# SwitchedATXBreakout.net
KiCad netlist of a schematic drawn in EAGLE
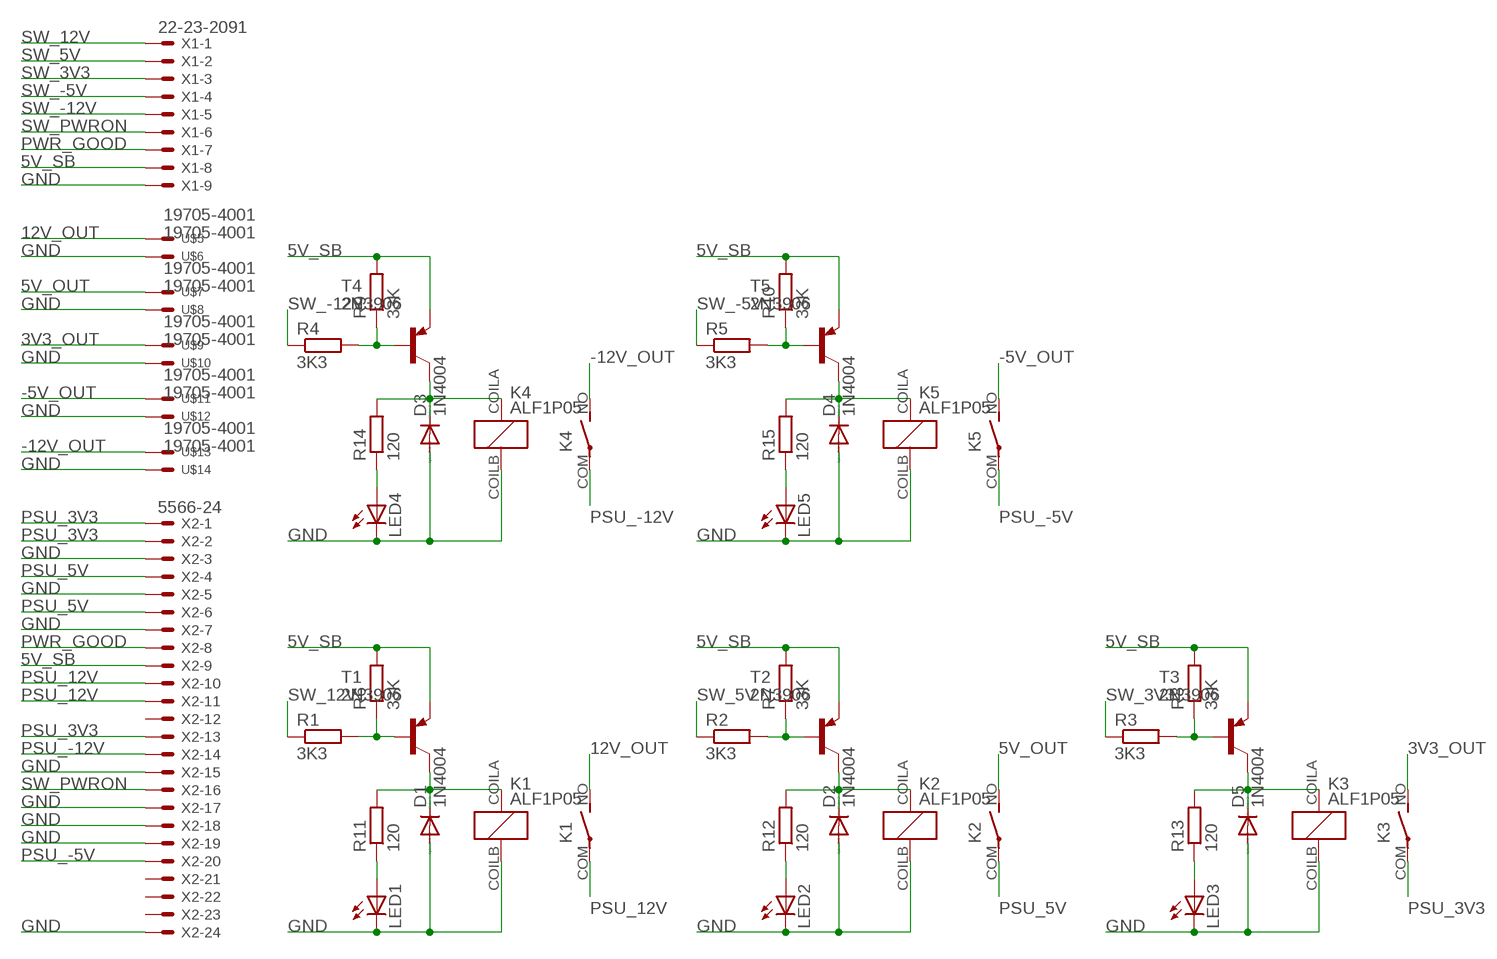
[diagram p0: schematic, sheet 1]

(export (version "E")
  (design (tool "Eeschema 10.0.6"))
  (components
    (comp (ref "D1")
      (value "1N4004")
      (footprint "eagle-import:DO41-10")
      (libsource (lib "eagle-import") (part "1N4004"))
    )
    (comp (ref "D2")
      (value "1N4004")
      (footprint "eagle-import:DO41-10")
      (libsource (lib "eagle-import") (part "1N4004"))
    )
    (comp (ref "D3")
      (value "1N4004")
      (footprint "eagle-import:DO41-10")
      (libsource (lib "eagle-import") (part "1N4004"))
    )
    (comp (ref "D4")
      (value "1N4004")
      (footprint "eagle-import:DO41-10")
      (libsource (lib "eagle-import") (part "1N4004"))
    )
    (comp (ref "D5")
      (value "1N4004")
      (footprint "eagle-import:DO41-10")
      (libsource (lib "eagle-import") (part "1N4004"))
    )
    (comp (ref "K1")
      (value "ALF1P05")
      (footprint "eagle-import:ALF")
      (libsource (lib "eagle-import") (part "ALF1P05"))
    )
    (comp (ref "K2")
      (value "ALF1P05")
      (footprint "eagle-import:ALF")
      (libsource (lib "eagle-import") (part "ALF1P05"))
    )
    (comp (ref "K3")
      (value "ALF1P05")
      (footprint "eagle-import:ALF")
      (libsource (lib "eagle-import") (part "ALF1P05"))
    )
    (comp (ref "K4")
      (value "ALF1P05")
      (footprint "eagle-import:ALF")
      (libsource (lib "eagle-import") (part "ALF1P05"))
    )
    (comp (ref "K5")
      (value "ALF1P05")
      (footprint "eagle-import:ALF")
      (libsource (lib "eagle-import") (part "ALF1P05"))
    )
    (comp (ref "LED1")
      (value "LED3MM")
      (footprint "eagle-import:LED3MM")
      (libsource (lib "eagle-import") (part "LED3MM"))
    )
    (comp (ref "LED2")
      (value "LED3MM")
      (footprint "eagle-import:LED3MM")
      (libsource (lib "eagle-import") (part "LED3MM"))
    )
    (comp (ref "LED3")
      (value "LED3MM")
      (footprint "eagle-import:LED3MM")
      (libsource (lib "eagle-import") (part "LED3MM"))
    )
    (comp (ref "LED4")
      (value "LED3MM")
      (footprint "eagle-import:LED3MM")
      (libsource (lib "eagle-import") (part "LED3MM"))
    )
    (comp (ref "LED5")
      (value "LED3MM")
      (footprint "eagle-import:LED3MM")
      (libsource (lib "eagle-import") (part "LED3MM"))
    )
    (comp (ref "R1")
      (value "3K3")
      (footprint "eagle-import:0204_7")
      (libsource (lib "eagle-import") (part "R-EU_0204/7"))
    )
    (comp (ref "R2")
      (value "3K3")
      (footprint "eagle-import:0204_7")
      (libsource (lib "eagle-import") (part "R-EU_0204/7"))
    )
    (comp (ref "R3")
      (value "3K3")
      (footprint "eagle-import:0204_7")
      (libsource (lib "eagle-import") (part "R-EU_0204/7"))
    )
    (comp (ref "R4")
      (value "3K3")
      (footprint "eagle-import:0204_7")
      (libsource (lib "eagle-import") (part "R-EU_0204/7"))
    )
    (comp (ref "R5")
      (value "3K3")
      (footprint "eagle-import:0204_7")
      (libsource (lib "eagle-import") (part "R-EU_0204/7"))
    )
    (comp (ref "R6")
      (value "33K")
      (footprint "eagle-import:0204_7")
      (libsource (lib "eagle-import") (part "R-EU_0204/7"))
    )
    (comp (ref "R7")
      (value "33K")
      (footprint "eagle-import:0204_7")
      (libsource (lib "eagle-import") (part "R-EU_0204/7"))
    )
    (comp (ref "R8")
      (value "33K")
      (footprint "eagle-import:0204_7")
      (libsource (lib "eagle-import") (part "R-EU_0204/7"))
    )
    (comp (ref "R9")
      (value "33K")
      (footprint "eagle-import:0204_7")
      (libsource (lib "eagle-import") (part "R-EU_0204/7"))
    )
    (comp (ref "R10")
      (value "33K")
      (footprint "eagle-import:0204_7")
      (libsource (lib "eagle-import") (part "R-EU_0204/7"))
    )
    (comp (ref "R11")
      (value "120")
      (footprint "eagle-import:0204_7")
      (libsource (lib "eagle-import") (part "R-EU_0204/7"))
    )
    (comp (ref "R12")
      (value "120")
      (footprint "eagle-import:0204_7")
      (libsource (lib "eagle-import") (part "R-EU_0204/7"))
    )
    (comp (ref "R13")
      (value "120")
      (footprint "eagle-import:0204_7")
      (libsource (lib "eagle-import") (part "R-EU_0204/7"))
    )
    (comp (ref "R14")
      (value "120")
      (footprint "eagle-import:0204_7")
      (libsource (lib "eagle-import") (part "R-EU_0204/7"))
    )
    (comp (ref "R15")
      (value "120")
      (footprint "eagle-import:0204_7")
      (libsource (lib "eagle-import") (part "R-EU_0204/7"))
    )
    (comp (ref "T1")
      (value "2N3906")
      (footprint "eagle-import:TO92-EBC")
      (libsource (lib "eagle-import") (part "-PNP-TO92-EBC"))
    )
    (comp (ref "T2")
      (value "2N3906")
      (footprint "eagle-import:TO92-EBC")
      (libsource (lib "eagle-import") (part "-PNP-TO92-EBC"))
    )
    (comp (ref "T3")
      (value "2N3906")
      (footprint "eagle-import:TO92-EBC")
      (libsource (lib "eagle-import") (part "-PNP-TO92-EBC"))
    )
    (comp (ref "T4")
      (value "2N3906")
      (footprint "eagle-import:TO92-EBC")
      (libsource (lib "eagle-import") (part "-PNP-TO92-EBC"))
    )
    (comp (ref "T5")
      (value "2N3906")
      (footprint "eagle-import:TO92-EBC")
      (libsource (lib "eagle-import") (part "-PNP-TO92-EBC"))
    )
    (comp (ref "U$5")
      (value "19705-4001")
      (footprint "eagle-import:19705-4001")
      (libsource (lib "eagle-import") (part "19705-4001"))
    )
    (comp (ref "U$6")
      (value "19705-4001")
      (footprint "eagle-import:19705-4001")
      (libsource (lib "eagle-import") (part "19705-4001"))
    )
    (comp (ref "U$7")
      (value "19705-4001")
      (footprint "eagle-import:19705-4001")
      (libsource (lib "eagle-import") (part "19705-4001"))
    )
    (comp (ref "U$8")
      (value "19705-4001")
      (footprint "eagle-import:19705-4001")
      (libsource (lib "eagle-import") (part "19705-4001"))
    )
    (comp (ref "U$9")
      (value "19705-4001")
      (footprint "eagle-import:19705-4001")
      (libsource (lib "eagle-import") (part "19705-4001"))
    )
    (comp (ref "U$10")
      (value "19705-4001")
      (footprint "eagle-import:19705-4001")
      (libsource (lib "eagle-import") (part "19705-4001"))
    )
    (comp (ref "U$11")
      (value "19705-4001")
      (footprint "eagle-import:19705-4001")
      (libsource (lib "eagle-import") (part "19705-4001"))
    )
    (comp (ref "U$12")
      (value "19705-4001")
      (footprint "eagle-import:19705-4001")
      (libsource (lib "eagle-import") (part "19705-4001"))
    )
    (comp (ref "U$13")
      (value "19705-4001")
      (footprint "eagle-import:19705-4001")
      (libsource (lib "eagle-import") (part "19705-4001"))
    )
    (comp (ref "U$14")
      (value "19705-4001")
      (footprint "eagle-import:19705-4001")
      (libsource (lib "eagle-import") (part "19705-4001"))
    )
    (comp (ref "X1")
      (value "22-23-2091")
      (footprint "eagle-import:22-23-2091")
      (fields (field (name "MF") "MOLEX"))
      (libsource (lib "eagle-import") (part "22-23-2091"))
    )
    (comp (ref "X2")
      (value "5566-24")
      (footprint "eagle-import:5566-24")
      (libsource (lib "eagle-import") (part "5566-24"))
    )
  )
  (nets
    (net (code "1") (name "/-5V_OUT") (class "Default")
      (node (ref "K5") (pin "NO") (pinfunction "S_NO") (pintype "passive"))
      (node (ref "U$11") (pin "P$1") (pinfunction "P$1_P$1") (pintype "bidirectional"))
      (node (ref "U$11") (pin "P$2") (pinfunction "P$1_P$2") (pintype "bidirectional"))
    )
    (net (code "2") (name "/-12V_OUT") (class "Default")
      (node (ref "K4") (pin "NO") (pinfunction "S_NO") (pintype "passive"))
      (node (ref "U$13") (pin "P$1") (pinfunction "P$1_P$1") (pintype "bidirectional"))
      (node (ref "U$13") (pin "P$2") (pinfunction "P$1_P$2") (pintype "bidirectional"))
    )
    (net (code "3") (name "/3V3_OUT") (class "Default")
      (node (ref "K3") (pin "NO") (pinfunction "S_NO") (pintype "passive"))
      (node (ref "U$9") (pin "P$1") (pinfunction "P$1_P$1") (pintype "bidirectional"))
      (node (ref "U$9") (pin "P$2") (pinfunction "P$1_P$2") (pintype "bidirectional"))
    )
    (net (code "4") (name "/5V_OUT") (class "Default")
      (node (ref "K2") (pin "NO") (pinfunction "S_NO") (pintype "passive"))
      (node (ref "U$7") (pin "P$1") (pinfunction "P$1_P$1") (pintype "bidirectional"))
      (node (ref "U$7") (pin "P$2") (pinfunction "P$1_P$2") (pintype "bidirectional"))
    )
    (net (code "5") (name "/5V_SB") (class "Default")
      (node (ref "R10") (pin "2") (pinfunction "2_2") (pintype "passive"))
      (node (ref "R6") (pin "2") (pinfunction "2_2") (pintype "passive"))
      (node (ref "R7") (pin "2") (pinfunction "2_2") (pintype "passive"))
      (node (ref "R8") (pin "2") (pinfunction "2_2") (pintype "passive"))
      (node (ref "R9") (pin "2") (pinfunction "2_2") (pintype "passive"))
      (node (ref "T1") (pin "E") (pinfunction "E_E") (pintype "passive"))
      (node (ref "T2") (pin "E") (pinfunction "E_E") (pintype "passive"))
      (node (ref "T3") (pin "E") (pinfunction "E_E") (pintype "passive"))
      (node (ref "T4") (pin "E") (pinfunction "E_E") (pintype "passive"))
      (node (ref "T5") (pin "E") (pinfunction "E_E") (pintype "passive"))
      (node (ref "X1") (pin "8") (pinfunction "S_8") (pintype "passive"))
      (node (ref "X2") (pin "9") (pinfunction "S_9") (pintype "passive"))
    )
    (net (code "6") (name "/12V_OUT") (class "Default")
      (node (ref "K1") (pin "NO") (pinfunction "S_NO") (pintype "passive"))
      (node (ref "U$5") (pin "P$1") (pinfunction "P$1_P$1") (pintype "bidirectional"))
      (node (ref "U$5") (pin "P$2") (pinfunction "P$1_P$2") (pintype "bidirectional"))
    )
    (net (code "7") (name "/GND") (class "Default")
      (node (ref "D1") (pin "A") (pinfunction "A_A") (pintype "passive"))
      (node (ref "D2") (pin "A") (pinfunction "A_A") (pintype "passive"))
      (node (ref "D3") (pin "A") (pinfunction "A_A") (pintype "passive"))
      (node (ref "D4") (pin "A") (pinfunction "A_A") (pintype "passive"))
      (node (ref "D5") (pin "A") (pinfunction "A_A") (pintype "passive"))
      (node (ref "K1") (pin "COILB") (pinfunction "2_COILB") (pintype "passive"))
      (node (ref "K2") (pin "COILB") (pinfunction "2_COILB") (pintype "passive"))
      (node (ref "K3") (pin "COILB") (pinfunction "2_COILB") (pintype "passive"))
      (node (ref "K4") (pin "COILB") (pinfunction "2_COILB") (pintype "passive"))
      (node (ref "K5") (pin "COILB") (pinfunction "2_COILB") (pintype "passive"))
      (node (ref "LED1") (pin "K") (pinfunction "C_K") (pintype "passive"))
      (node (ref "LED2") (pin "K") (pinfunction "C_K") (pintype "passive"))
      (node (ref "LED3") (pin "K") (pinfunction "C_K") (pintype "passive"))
      (node (ref "LED4") (pin "K") (pinfunction "C_K") (pintype "passive"))
      (node (ref "LED5") (pin "K") (pinfunction "C_K") (pintype "passive"))
      (node (ref "U$10") (pin "P$1") (pinfunction "P$1_P$1") (pintype "bidirectional"))
      (node (ref "U$10") (pin "P$2") (pinfunction "P$1_P$2") (pintype "bidirectional"))
      (node (ref "U$12") (pin "P$1") (pinfunction "P$1_P$1") (pintype "bidirectional"))
      (node (ref "U$12") (pin "P$2") (pinfunction "P$1_P$2") (pintype "bidirectional"))
      (node (ref "U$14") (pin "P$1") (pinfunction "P$1_P$1") (pintype "bidirectional"))
      (node (ref "U$14") (pin "P$2") (pinfunction "P$1_P$2") (pintype "bidirectional"))
      (node (ref "U$6") (pin "P$1") (pinfunction "P$1_P$1") (pintype "bidirectional"))
      (node (ref "U$6") (pin "P$2") (pinfunction "P$1_P$2") (pintype "bidirectional"))
      (node (ref "U$8") (pin "P$1") (pinfunction "P$1_P$1") (pintype "bidirectional"))
      (node (ref "U$8") (pin "P$2") (pinfunction "P$1_P$2") (pintype "bidirectional"))
      (node (ref "X1") (pin "9") (pinfunction "S_9") (pintype "passive"))
      (node (ref "X2") (pin "15") (pinfunction "S_15") (pintype "passive"))
      (node (ref "X2") (pin "17") (pinfunction "S_17") (pintype "passive"))
      (node (ref "X2") (pin "18") (pinfunction "S_18") (pintype "passive"))
      (node (ref "X2") (pin "19") (pinfunction "S_19") (pintype "passive"))
      (node (ref "X2") (pin "24") (pinfunction "S_24") (pintype "passive"))
      (node (ref "X2") (pin "3") (pinfunction "S_3") (pintype "passive"))
      (node (ref "X2") (pin "5") (pinfunction "S_5") (pintype "passive"))
      (node (ref "X2") (pin "7") (pinfunction "S_7") (pintype "passive"))
    )
    (net (code "8") (name "/PSU_-5V") (class "Default")
      (node (ref "K5") (pin "COM") (pinfunction "P_COM") (pintype "passive"))
      (node (ref "X2") (pin "20") (pinfunction "S_20") (pintype "passive"))
    )
    (net (code "9") (name "/PSU_-12V") (class "Default")
      (node (ref "K4") (pin "COM") (pinfunction "P_COM") (pintype "passive"))
      (node (ref "X2") (pin "14") (pinfunction "S_14") (pintype "passive"))
    )
    (net (code "10") (name "/PSU_3V3") (class "Default")
      (node (ref "K3") (pin "COM") (pinfunction "P_COM") (pintype "passive"))
      (node (ref "X2") (pin "1") (pinfunction "S_1") (pintype "passive"))
      (node (ref "X2") (pin "13") (pinfunction "S_13") (pintype "passive"))
      (node (ref "X2") (pin "2") (pinfunction "S_2") (pintype "passive"))
    )
    (net (code "11") (name "/PSU_5V") (class "Default")
      (node (ref "K2") (pin "COM") (pinfunction "P_COM") (pintype "passive"))
      (node (ref "X2") (pin "4") (pinfunction "S_4") (pintype "passive"))
      (node (ref "X2") (pin "6") (pinfunction "S_6") (pintype "passive"))
    )
    (net (code "12") (name "/PSU_12V") (class "Default")
      (node (ref "K1") (pin "COM") (pinfunction "P_COM") (pintype "passive"))
      (node (ref "X2") (pin "10") (pinfunction "S_10") (pintype "passive"))
      (node (ref "X2") (pin "11") (pinfunction "S_11") (pintype "passive"))
    )
    (net (code "13") (name "/PWR_GOOD") (class "Default")
      (node (ref "X1") (pin "7") (pinfunction "S_7") (pintype "passive"))
      (node (ref "X2") (pin "8") (pinfunction "S_8") (pintype "passive"))
    )
    (net (code "14") (name "/SW_-5V") (class "Default")
      (node (ref "R5") (pin "1") (pinfunction "1_1") (pintype "passive"))
      (node (ref "X1") (pin "4") (pinfunction "S_4") (pintype "passive"))
    )
    (net (code "15") (name "/SW_-12V") (class "Default")
      (node (ref "R4") (pin "1") (pinfunction "1_1") (pintype "passive"))
      (node (ref "X1") (pin "5") (pinfunction "S_5") (pintype "passive"))
    )
    (net (code "16") (name "/SW_3V3") (class "Default")
      (node (ref "R3") (pin "1") (pinfunction "1_1") (pintype "passive"))
      (node (ref "X1") (pin "3") (pinfunction "S_3") (pintype "passive"))
    )
    (net (code "17") (name "/SW_5V") (class "Default")
      (node (ref "R2") (pin "1") (pinfunction "1_1") (pintype "passive"))
      (node (ref "X1") (pin "2") (pinfunction "S_2") (pintype "passive"))
    )
    (net (code "18") (name "/SW_12V") (class "Default")
      (node (ref "R1") (pin "1") (pinfunction "1_1") (pintype "passive"))
      (node (ref "X1") (pin "1") (pinfunction "S_1") (pintype "passive"))
    )
    (net (code "19") (name "/SW_PWRON") (class "Default")
      (node (ref "X1") (pin "6") (pinfunction "S_6") (pintype "passive"))
      (node (ref "X2") (pin "16") (pinfunction "S_16") (pintype "passive"))
    )
    (net (code "20") (name "Net-(K1B-1)") (class "Default")
      (node (ref "D1") (pin "C") (pinfunction "C_C") (pintype "passive"))
      (node (ref "K1") (pin "COILA") (pinfunction "1_COILA") (pintype "passive"))
      (node (ref "R11") (pin "2") (pinfunction "2_2") (pintype "passive"))
      (node (ref "T1") (pin "C") (pinfunction "C_C") (pintype "passive"))
    )
    (net (code "21") (name "Net-(K2B-1)") (class "Default")
      (node (ref "D2") (pin "C") (pinfunction "C_C") (pintype "passive"))
      (node (ref "K2") (pin "COILA") (pinfunction "1_COILA") (pintype "passive"))
      (node (ref "R12") (pin "2") (pinfunction "2_2") (pintype "passive"))
      (node (ref "T2") (pin "C") (pinfunction "C_C") (pintype "passive"))
    )
    (net (code "22") (name "Net-(K3B-1)") (class "Default")
      (node (ref "D5") (pin "C") (pinfunction "C_C") (pintype "passive"))
      (node (ref "K3") (pin "COILA") (pinfunction "1_COILA") (pintype "passive"))
      (node (ref "R13") (pin "2") (pinfunction "2_2") (pintype "passive"))
      (node (ref "T3") (pin "C") (pinfunction "C_C") (pintype "passive"))
    )
    (net (code "23") (name "Net-(K4B-1)") (class "Default")
      (node (ref "D3") (pin "C") (pinfunction "C_C") (pintype "passive"))
      (node (ref "K4") (pin "COILA") (pinfunction "1_COILA") (pintype "passive"))
      (node (ref "R14") (pin "2") (pinfunction "2_2") (pintype "passive"))
      (node (ref "T4") (pin "C") (pinfunction "C_C") (pintype "passive"))
    )
    (net (code "24") (name "Net-(K5B-1)") (class "Default")
      (node (ref "D4") (pin "C") (pinfunction "C_C") (pintype "passive"))
      (node (ref "K5") (pin "COILA") (pinfunction "1_COILA") (pintype "passive"))
      (node (ref "R15") (pin "2") (pinfunction "2_2") (pintype "passive"))
      (node (ref "T5") (pin "C") (pinfunction "C_C") (pintype "passive"))
    )
    (net (code "25") (name "Net-(LED1-PadA)") (class "Default")
      (node (ref "LED1") (pin "A") (pinfunction "A_A") (pintype "passive"))
      (node (ref "R11") (pin "1") (pinfunction "1_1") (pintype "passive"))
    )
    (net (code "26") (name "Net-(LED2-PadA)") (class "Default")
      (node (ref "LED2") (pin "A") (pinfunction "A_A") (pintype "passive"))
      (node (ref "R12") (pin "1") (pinfunction "1_1") (pintype "passive"))
    )
    (net (code "27") (name "Net-(LED3-PadA)") (class "Default")
      (node (ref "LED3") (pin "A") (pinfunction "A_A") (pintype "passive"))
      (node (ref "R13") (pin "1") (pinfunction "1_1") (pintype "passive"))
    )
    (net (code "28") (name "Net-(LED4-PadA)") (class "Default")
      (node (ref "LED4") (pin "A") (pinfunction "A_A") (pintype "passive"))
      (node (ref "R14") (pin "1") (pinfunction "1_1") (pintype "passive"))
    )
    (net (code "29") (name "Net-(LED5-PadA)") (class "Default")
      (node (ref "LED5") (pin "A") (pinfunction "A_A") (pintype "passive"))
      (node (ref "R15") (pin "1") (pinfunction "1_1") (pintype "passive"))
    )
    (net (code "30") (name "Net-(R1-Pad2)") (class "Default")
      (node (ref "R1") (pin "2") (pinfunction "2_2") (pintype "passive"))
      (node (ref "R6") (pin "1") (pinfunction "1_1") (pintype "passive"))
      (node (ref "T1") (pin "B") (pinfunction "B_B") (pintype "passive"))
    )
    (net (code "31") (name "Net-(R2-Pad2)") (class "Default")
      (node (ref "R2") (pin "2") (pinfunction "2_2") (pintype "passive"))
      (node (ref "R7") (pin "1") (pinfunction "1_1") (pintype "passive"))
      (node (ref "T2") (pin "B") (pinfunction "B_B") (pintype "passive"))
    )
    (net (code "32") (name "Net-(R3-Pad2)") (class "Default")
      (node (ref "R3") (pin "2") (pinfunction "2_2") (pintype "passive"))
      (node (ref "R8") (pin "1") (pinfunction "1_1") (pintype "passive"))
      (node (ref "T3") (pin "B") (pinfunction "B_B") (pintype "passive"))
    )
    (net (code "33") (name "Net-(R4-Pad2)") (class "Default")
      (node (ref "R4") (pin "2") (pinfunction "2_2") (pintype "passive"))
      (node (ref "R9") (pin "1") (pinfunction "1_1") (pintype "passive"))
      (node (ref "T4") (pin "B") (pinfunction "B_B") (pintype "passive"))
    )
    (net (code "34") (name "Net-(R10-Pad1)") (class "Default")
      (node (ref "R10") (pin "1") (pinfunction "1_1") (pintype "passive"))
      (node (ref "R5") (pin "2") (pinfunction "2_2") (pintype "passive"))
      (node (ref "T5") (pin "B") (pinfunction "B_B") (pintype "passive"))
    )
    (net (code "35") (name "unconnected-(X2D-S-Pad12)") (class "Default")
      (node (ref "X2") (pin "12") (pinfunction "S_12") (pintype "passive"))
    )
    (net (code "36") (name "unconnected-(X2N-S-Pad21)") (class "Default")
      (node (ref "X2") (pin "21") (pinfunction "S_21") (pintype "passive"))
    )
    (net (code "37") (name "unconnected-(X2O-S-Pad22)") (class "Default")
      (node (ref "X2") (pin "22") (pinfunction "S_22") (pintype "passive"))
    )
    (net (code "38") (name "unconnected-(X2P-S-Pad23)") (class "Default")
      (node (ref "X2") (pin "23") (pinfunction "S_23") (pintype "passive"))
    )
  )
)
